# shemLamps.net
KiCad netlist of a schematic drawn in EAGLE
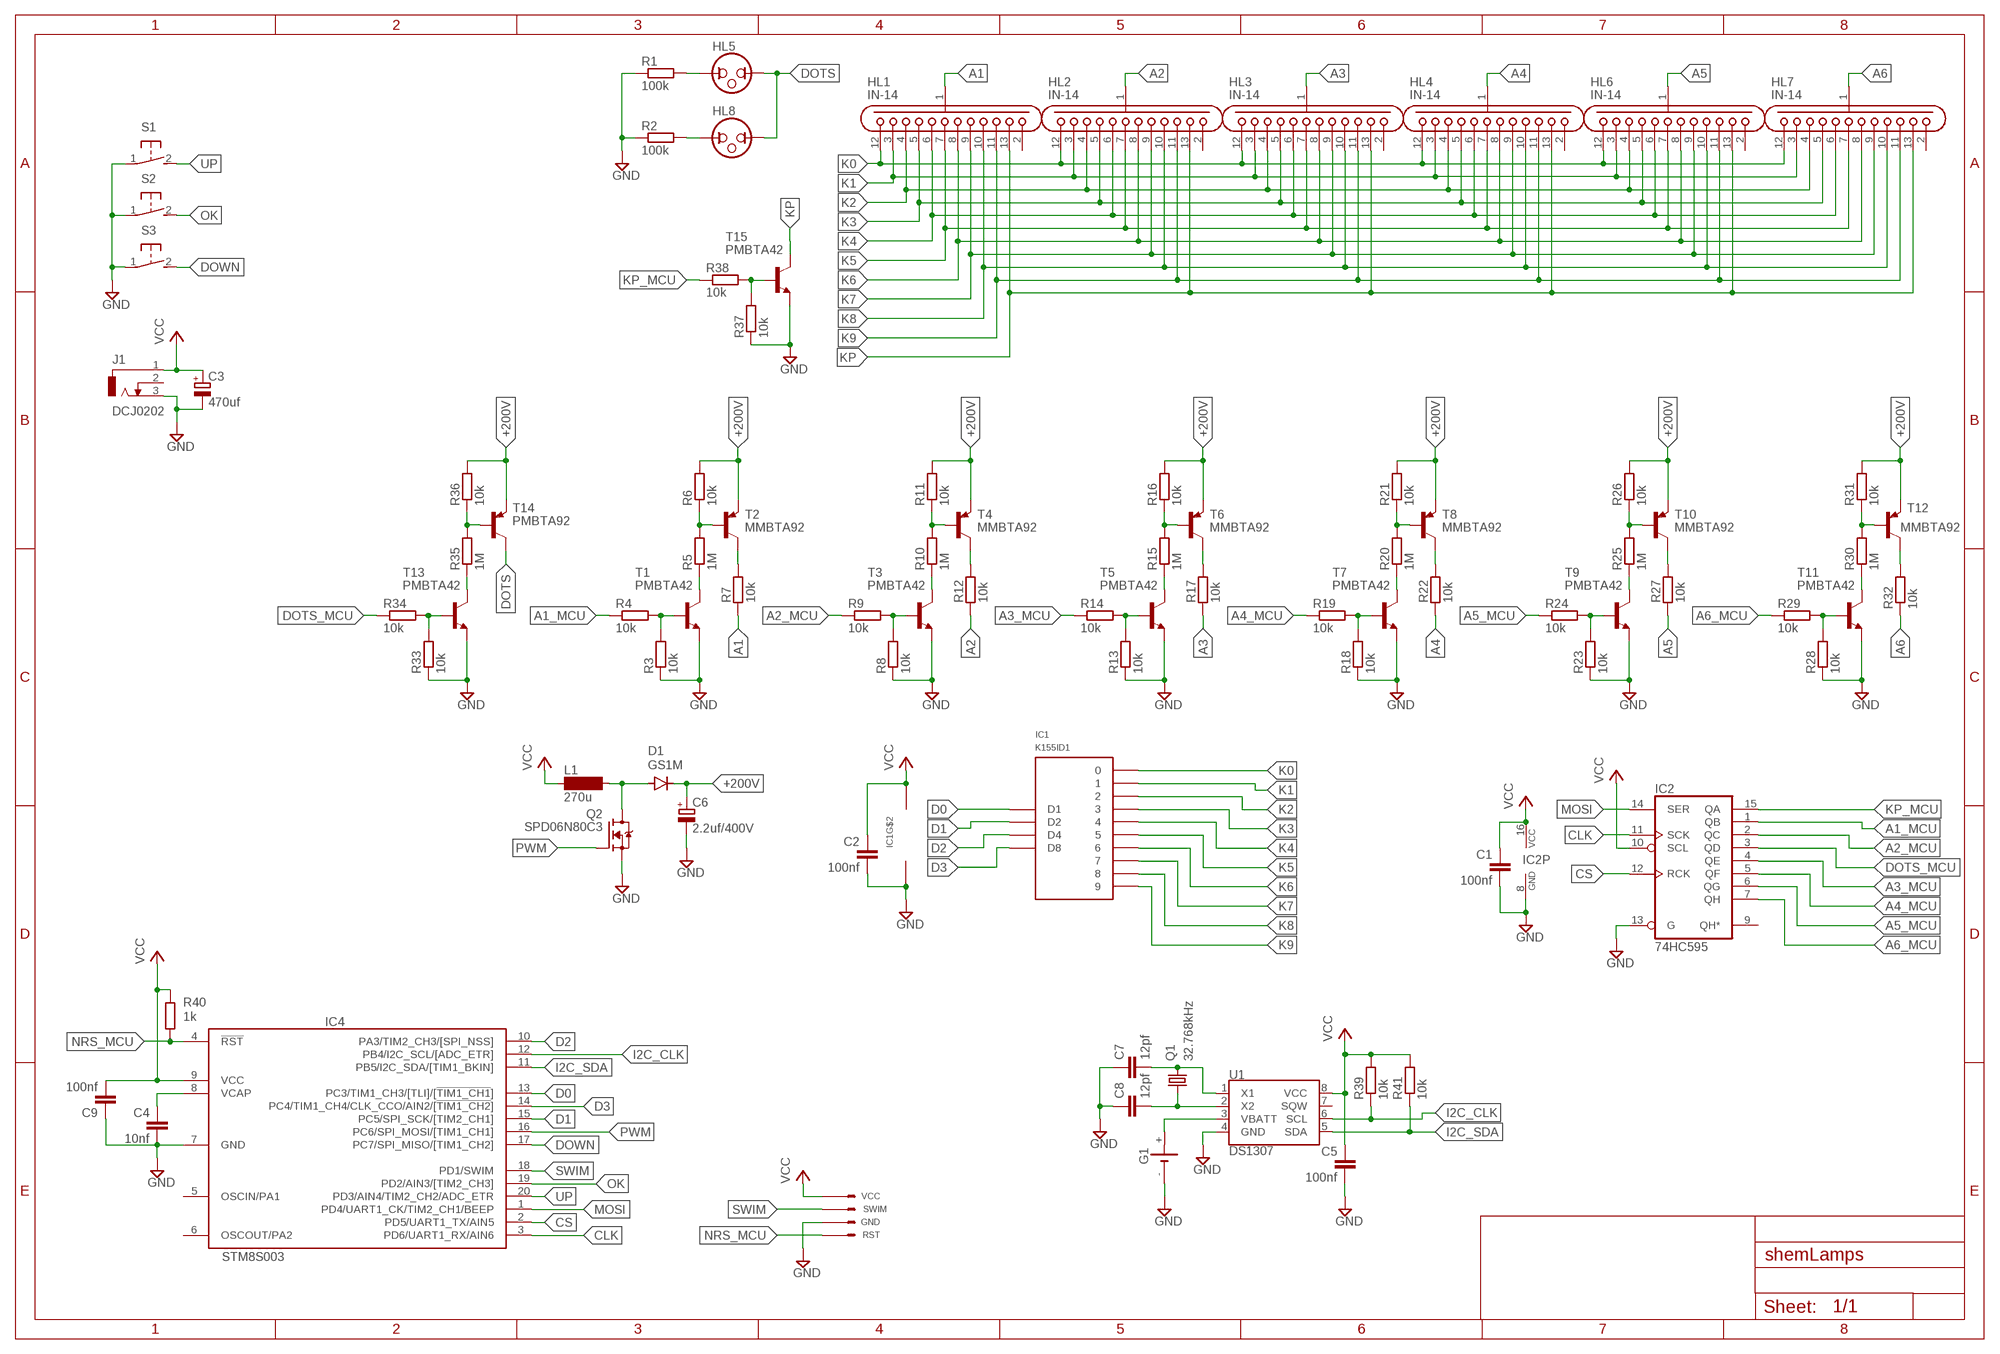
[diagram p0: schematic, sheet 1]

(export (version "E")
  (design (tool "Eeschema 10.0.6"))
  (components
    (comp (ref "C1")
      (value "100nf")
      (footprint "eagle-import:C0805")
      (libsource (lib "eagle-import") (part "CAP"))
    )
    (comp (ref "C2")
      (value "100nf")
      (footprint "eagle-import:C0805")
      (libsource (lib "eagle-import") (part "CAP"))
    )
    (comp (ref "C3")
      (value "470uf")
      (footprint "eagle-import:E3,5-8")
      (libsource (lib "eagle-import") (part "CPOL-EUE3.5-8"))
    )
    (comp (ref "C4")
      (value "10nf")
      (footprint "eagle-import:C0805")
      (libsource (lib "eagle-import") (part "CAP"))
    )
    (comp (ref "C5")
      (value "100nf")
      (footprint "eagle-import:C0805")
      (libsource (lib "eagle-import") (part "CAP"))
    )
    (comp (ref "C6")
      (value "2.2uf/400V")
      (footprint "eagle-import:E3,5-8")
      (libsource (lib "eagle-import") (part "CPOL-EUE3.5-8"))
    )
    (comp (ref "C7")
      (value "12pf")
      (footprint "eagle-import:C0805")
      (libsource (lib "eagle-import") (part "CAP"))
    )
    (comp (ref "C8")
      (value "12pf")
      (footprint "eagle-import:C0805")
      (libsource (lib "eagle-import") (part "CAP"))
    )
    (comp (ref "C9")
      (value "100nf")
      (footprint "eagle-import:C0805")
      (libsource (lib "eagle-import") (part "CAP"))
    )
    (comp (ref "D1")
      (value "GS1M")
      (footprint "eagle-import:DO-214AC")
      (libsource (lib "eagle-import") (part "DIODE-DO-214AC"))
    )
    (comp (ref "G1")
      (value "BATTERY")
      (footprint "eagle-import:CH291-1220LF_W")
      (libsource (lib "eagle-import") (part "BATTERY"))
    )
    (comp (ref "HL1")
      (value "IN-14")
      (footprint "eagle-import:IN-14")
      (libsource (lib "eagle-import") (part "IN-14"))
    )
    (comp (ref "HL2")
      (value "IN-14")
      (footprint "eagle-import:IN-14")
      (libsource (lib "eagle-import") (part "IN-14"))
    )
    (comp (ref "HL3")
      (value "IN-14")
      (footprint "eagle-import:IN-14")
      (libsource (lib "eagle-import") (part "IN-14"))
    )
    (comp (ref "HL4")
      (value "IN-14")
      (footprint "eagle-import:IN-14")
      (libsource (lib "eagle-import") (part "IN-14"))
    )
    (comp (ref "HL5")
      (value "NEON_LAMP")
      (footprint "eagle-import:NEON_LAMP")
      (libsource (lib "eagle-import") (part "NEON_LAMP"))
    )
    (comp (ref "HL6")
      (value "IN-14")
      (footprint "eagle-import:IN-14")
      (libsource (lib "eagle-import") (part "IN-14"))
    )
    (comp (ref "HL7")
      (value "IN-14")
      (footprint "eagle-import:IN-14")
      (libsource (lib "eagle-import") (part "IN-14"))
    )
    (comp (ref "HL8")
      (value "NEON_LAMP")
      (footprint "eagle-import:NEON_LAMP")
      (libsource (lib "eagle-import") (part "NEON_LAMP"))
    )
    (comp (ref "IC1")
      (value "K155ID1")
      (footprint "eagle-import:DIL16")
      (libsource (lib "eagle-import") (part "K155ID1"))
    )
    (comp (ref "IC2")
      (value "74HC595")
      (footprint "eagle-import:TSSOP16L")
      (libsource (lib "eagle-import") (part "74HC595"))
    )
    (comp (ref "IC4")
      (value "STM8S003")
      (footprint "eagle-import:TSSOP-20")
      (libsource (lib "eagle-import") (part "STM8S003"))
    )
    (comp (ref "J1")
      (value "DCJ0202")
      (footprint "eagle-import:DCJ0202")
      (libsource (lib "eagle-import") (part "DCJ0202"))
    )
    (comp (ref "L1")
      (value "270u")
      (footprint "eagle-import:BS11")
      (libsource (lib "eagle-import") (part "BS11"))
    )
    (comp (ref "Q1")
      (value "32.768kHz")
      (footprint "eagle-import:TC26H")
      (libsource (lib "eagle-import") (part "CRYSTALTC26H"))
    )
    (comp (ref "Q2")
      (value "SPD06N80C3")
      (footprint "eagle-import:TO252")
      (libsource (lib "eagle-import") (part "SPD06N80C3"))
    )
    (comp (ref "R1")
      (value "100k")
      (footprint "eagle-import:0207_10")
      (libsource (lib "eagle-import") (part "R-EU_0207/10"))
    )
    (comp (ref "R2")
      (value "100k")
      (footprint "eagle-import:0207_10")
      (libsource (lib "eagle-import") (part "R-EU_0207/10"))
    )
    (comp (ref "R3")
      (value "10k")
      (footprint "eagle-import:R0805")
      (libsource (lib "eagle-import") (part "RES"))
    )
    (comp (ref "R4")
      (value "10k")
      (footprint "eagle-import:R0805")
      (libsource (lib "eagle-import") (part "RES"))
    )
    (comp (ref "R5")
      (value "1M")
      (footprint "eagle-import:R0805")
      (libsource (lib "eagle-import") (part "RES"))
    )
    (comp (ref "R6")
      (value "10k")
      (footprint "eagle-import:R0805")
      (libsource (lib "eagle-import") (part "RES"))
    )
    (comp (ref "R7")
      (value "10k")
      (footprint "eagle-import:R0805")
      (libsource (lib "eagle-import") (part "RES"))
    )
    (comp (ref "R8")
      (value "10k")
      (footprint "eagle-import:R0805")
      (libsource (lib "eagle-import") (part "RES"))
    )
    (comp (ref "R9")
      (value "10k")
      (footprint "eagle-import:R0805")
      (libsource (lib "eagle-import") (part "RES"))
    )
    (comp (ref "R10")
      (value "1M")
      (footprint "eagle-import:R0805")
      (libsource (lib "eagle-import") (part "RES"))
    )
    (comp (ref "R11")
      (value "10k")
      (footprint "eagle-import:R0805")
      (libsource (lib "eagle-import") (part "RES"))
    )
    (comp (ref "R12")
      (value "10k")
      (footprint "eagle-import:R0805")
      (libsource (lib "eagle-import") (part "RES"))
    )
    (comp (ref "R13")
      (value "10k")
      (footprint "eagle-import:R0805")
      (libsource (lib "eagle-import") (part "RES"))
    )
    (comp (ref "R14")
      (value "10k")
      (footprint "eagle-import:R0805")
      (libsource (lib "eagle-import") (part "RES"))
    )
    (comp (ref "R15")
      (value "1M")
      (footprint "eagle-import:R0805")
      (libsource (lib "eagle-import") (part "RES"))
    )
    (comp (ref "R16")
      (value "10k")
      (footprint "eagle-import:R0805")
      (libsource (lib "eagle-import") (part "RES"))
    )
    (comp (ref "R17")
      (value "10k")
      (footprint "eagle-import:R0805")
      (libsource (lib "eagle-import") (part "RES"))
    )
    (comp (ref "R18")
      (value "10k")
      (footprint "eagle-import:R0805")
      (libsource (lib "eagle-import") (part "RES"))
    )
    (comp (ref "R19")
      (value "10k")
      (footprint "eagle-import:R0805")
      (libsource (lib "eagle-import") (part "RES"))
    )
    (comp (ref "R20")
      (value "1M")
      (footprint "eagle-import:R0805")
      (libsource (lib "eagle-import") (part "RES"))
    )
    (comp (ref "R21")
      (value "10k")
      (footprint "eagle-import:R0805")
      (libsource (lib "eagle-import") (part "RES"))
    )
    (comp (ref "R22")
      (value "10k")
      (footprint "eagle-import:R0805")
      (libsource (lib "eagle-import") (part "RES"))
    )
    (comp (ref "R23")
      (value "10k")
      (footprint "eagle-import:R0805")
      (libsource (lib "eagle-import") (part "RES"))
    )
    (comp (ref "R24")
      (value "10k")
      (footprint "eagle-import:R0805")
      (libsource (lib "eagle-import") (part "RES"))
    )
    (comp (ref "R25")
      (value "1M")
      (footprint "eagle-import:R0805")
      (libsource (lib "eagle-import") (part "RES"))
    )
    (comp (ref "R26")
      (value "10k")
      (footprint "eagle-import:R0805")
      (libsource (lib "eagle-import") (part "RES"))
    )
    (comp (ref "R27")
      (value "10k")
      (footprint "eagle-import:R0805")
      (libsource (lib "eagle-import") (part "RES"))
    )
    (comp (ref "R28")
      (value "10k")
      (footprint "eagle-import:R0805")
      (libsource (lib "eagle-import") (part "RES"))
    )
    (comp (ref "R29")
      (value "10k")
      (footprint "eagle-import:R0805")
      (libsource (lib "eagle-import") (part "RES"))
    )
    (comp (ref "R30")
      (value "1M")
      (footprint "eagle-import:R0805")
      (libsource (lib "eagle-import") (part "RES"))
    )
    (comp (ref "R31")
      (value "10k")
      (footprint "eagle-import:R0805")
      (libsource (lib "eagle-import") (part "RES"))
    )
    (comp (ref "R32")
      (value "10k")
      (footprint "eagle-import:R0805")
      (libsource (lib "eagle-import") (part "RES"))
    )
    (comp (ref "R33")
      (value "10k")
      (footprint "eagle-import:R0805")
      (libsource (lib "eagle-import") (part "RES"))
    )
    (comp (ref "R34")
      (value "10k")
      (footprint "eagle-import:R0805")
      (libsource (lib "eagle-import") (part "RES"))
    )
    (comp (ref "R35")
      (value "1M")
      (footprint "eagle-import:R0805")
      (libsource (lib "eagle-import") (part "RES"))
    )
    (comp (ref "R36")
      (value "10k")
      (footprint "eagle-import:R0805")
      (libsource (lib "eagle-import") (part "RES"))
    )
    (comp (ref "R37")
      (value "10k")
      (footprint "eagle-import:R0805")
      (libsource (lib "eagle-import") (part "RES"))
    )
    (comp (ref "R38")
      (value "10k")
      (footprint "eagle-import:R0805")
      (libsource (lib "eagle-import") (part "RES"))
    )
    (comp (ref "R39")
      (value "10k")
      (footprint "eagle-import:R0805")
      (libsource (lib "eagle-import") (part "RES"))
    )
    (comp (ref "R40")
      (value "1k")
      (footprint "eagle-import:R0805")
      (libsource (lib "eagle-import") (part "RES"))
    )
    (comp (ref "R41")
      (value "10k")
      (footprint "eagle-import:R0805")
      (libsource (lib "eagle-import") (part "RES"))
    )
    (comp (ref "S1")
      (value "31-XX")
      (footprint "eagle-import:B3F-31XX")
      (fields (field (name "MPN") "B3F-3100"))
      (libsource (lib "eagle-import") (part "31-XX"))
    )
    (comp (ref "S2")
      (value "31-XX")
      (footprint "eagle-import:B3F-31XX")
      (fields (field (name "MPN") "B3F-3100"))
      (libsource (lib "eagle-import") (part "31-XX"))
    )
    (comp (ref "S3")
      (value "31-XX")
      (footprint "eagle-import:B3F-31XX")
      (fields (field (name "MPN") "B3F-3100"))
      (libsource (lib "eagle-import") (part "31-XX"))
    )
    (comp (ref "SV1")
      (value "SWIM")
      (footprint "eagle-import:SWIM")
      (libsource (lib "eagle-import") (part "SWIM"))
    )
    (comp (ref "T1")
      (value "PMBTA42")
      (footprint "eagle-import:SOT23-BEC")
      (libsource (lib "eagle-import") (part "-NPN-SOT23-BECBC817-16"))
    )
    (comp (ref "T2")
      (value "MMBTA92")
      (footprint "eagle-import:SOT23-BEC")
      (libsource (lib "eagle-import") (part "-PNP-SOT23-BECBC807-16"))
    )
    (comp (ref "T3")
      (value "PMBTA42")
      (footprint "eagle-import:SOT23-BEC")
      (libsource (lib "eagle-import") (part "-NPN-SOT23-BECBC817-16"))
    )
    (comp (ref "T4")
      (value "MMBTA92")
      (footprint "eagle-import:SOT23-BEC")
      (libsource (lib "eagle-import") (part "-PNP-SOT23-BECBC807-16"))
    )
    (comp (ref "T5")
      (value "PMBTA42")
      (footprint "eagle-import:SOT23-BEC")
      (libsource (lib "eagle-import") (part "-NPN-SOT23-BECBC817-16"))
    )
    (comp (ref "T6")
      (value "MMBTA92")
      (footprint "eagle-import:SOT23-BEC")
      (libsource (lib "eagle-import") (part "-PNP-SOT23-BECBC807-16"))
    )
    (comp (ref "T7")
      (value "PMBTA42")
      (footprint "eagle-import:SOT23-BEC")
      (libsource (lib "eagle-import") (part "-NPN-SOT23-BECBC817-16"))
    )
    (comp (ref "T8")
      (value "MMBTA92")
      (footprint "eagle-import:SOT23-BEC")
      (libsource (lib "eagle-import") (part "-PNP-SOT23-BECBC807-16"))
    )
    (comp (ref "T9")
      (value "PMBTA42")
      (footprint "eagle-import:SOT23-BEC")
      (libsource (lib "eagle-import") (part "-NPN-SOT23-BECBC817-16"))
    )
    (comp (ref "T10")
      (value "MMBTA92")
      (footprint "eagle-import:SOT23-BEC")
      (libsource (lib "eagle-import") (part "-PNP-SOT23-BECBC807-16"))
    )
    (comp (ref "T11")
      (value "PMBTA42")
      (footprint "eagle-import:SOT23-BEC")
      (libsource (lib "eagle-import") (part "-NPN-SOT23-BECBC817-16"))
    )
    (comp (ref "T12")
      (value "MMBTA92")
      (footprint "eagle-import:SOT23-BEC")
      (libsource (lib "eagle-import") (part "-PNP-SOT23-BECBC807-16"))
    )
    (comp (ref "T13")
      (value "PMBTA42")
      (footprint "eagle-import:SOT23-BEC")
      (libsource (lib "eagle-import") (part "-NPN-SOT23-BECBC817-16"))
    )
    (comp (ref "T14")
      (value "PMBTA92")
      (footprint "eagle-import:SOT23-BEC")
      (libsource (lib "eagle-import") (part "-PNP-SOT23-BECBC807-16"))
    )
    (comp (ref "T15")
      (value "PMBTA42")
      (footprint "eagle-import:SOT23-BEC")
      (libsource (lib "eagle-import") (part "-NPN-SOT23-BECBC817-16"))
    )
    (comp (ref "U1")
      (value "DS1307")
      (footprint "eagle-import:SO08")
      (libsource (lib "eagle-import") (part "DS1307"))
    )
  )
  (nets
    (net (code "1") (name "+200V") (class "Default")
      (node (ref "C6") (pin "+") (pinfunction "+_+") (pintype "passive"))
      (node (ref "D1") (pin "C") (pinfunction "C_C") (pintype "passive"))
      (node (ref "R11") (pin "2") (pinfunction "2_2") (pintype "passive"))
      (node (ref "R16") (pin "2") (pinfunction "2_2") (pintype "passive"))
      (node (ref "R21") (pin "2") (pinfunction "2_2") (pintype "passive"))
      (node (ref "R26") (pin "2") (pinfunction "2_2") (pintype "passive"))
      (node (ref "R31") (pin "2") (pinfunction "2_2") (pintype "passive"))
      (node (ref "R36") (pin "2") (pinfunction "2_2") (pintype "passive"))
      (node (ref "R6") (pin "2") (pinfunction "2_2") (pintype "passive"))
      (node (ref "T10") (pin "E") (pinfunction "E_E") (pintype "passive"))
      (node (ref "T12") (pin "E") (pinfunction "E_E") (pintype "passive"))
      (node (ref "T14") (pin "E") (pinfunction "E_E") (pintype "passive"))
      (node (ref "T2") (pin "E") (pinfunction "E_E") (pintype "passive"))
      (node (ref "T4") (pin "E") (pinfunction "E_E") (pintype "passive"))
      (node (ref "T6") (pin "E") (pinfunction "E_E") (pintype "passive"))
      (node (ref "T8") (pin "E") (pinfunction "E_E") (pintype "passive"))
    )
    (net (code "2") (name "A1") (class "Default")
      (node (ref "HL1") (pin "1") (pinfunction "A_1") (pintype "passive"))
      (node (ref "R7") (pin "1") (pinfunction "1_1") (pintype "passive"))
    )
    (net (code "3") (name "A1_MCU") (class "Default")
      (node (ref "IC2") (pin "1") (pinfunction "QB_1") (pintype "tri_state"))
      (node (ref "R4") (pin "1") (pinfunction "1_1") (pintype "passive"))
    )
    (net (code "4") (name "A2") (class "Default")
      (node (ref "HL2") (pin "1") (pinfunction "A_1") (pintype "passive"))
      (node (ref "R12") (pin "1") (pinfunction "1_1") (pintype "passive"))
    )
    (net (code "5") (name "A2_MCU") (class "Default")
      (node (ref "IC2") (pin "2") (pinfunction "QC_2") (pintype "tri_state"))
      (node (ref "R9") (pin "1") (pinfunction "1_1") (pintype "passive"))
    )
    (net (code "6") (name "A3") (class "Default")
      (node (ref "HL3") (pin "1") (pinfunction "A_1") (pintype "passive"))
      (node (ref "R17") (pin "1") (pinfunction "1_1") (pintype "passive"))
    )
    (net (code "7") (name "A3_MCU") (class "Default")
      (node (ref "IC2") (pin "4") (pinfunction "QE_4") (pintype "tri_state"))
      (node (ref "R14") (pin "1") (pinfunction "1_1") (pintype "passive"))
    )
    (net (code "8") (name "A4") (class "Default")
      (node (ref "HL4") (pin "1") (pinfunction "A_1") (pintype "passive"))
      (node (ref "R22") (pin "1") (pinfunction "1_1") (pintype "passive"))
    )
    (net (code "9") (name "A4_MCU") (class "Default")
      (node (ref "IC2") (pin "5") (pinfunction "QF_5") (pintype "tri_state"))
      (node (ref "R19") (pin "1") (pinfunction "1_1") (pintype "passive"))
    )
    (net (code "10") (name "A5") (class "Default")
      (node (ref "HL6") (pin "1") (pinfunction "A_1") (pintype "passive"))
      (node (ref "R27") (pin "1") (pinfunction "1_1") (pintype "passive"))
    )
    (net (code "11") (name "A5_MCU") (class "Default")
      (node (ref "IC2") (pin "6") (pinfunction "QG_6") (pintype "tri_state"))
      (node (ref "R24") (pin "1") (pinfunction "1_1") (pintype "passive"))
    )
    (net (code "12") (name "A6") (class "Default")
      (node (ref "HL7") (pin "1") (pinfunction "A_1") (pintype "passive"))
      (node (ref "R32") (pin "1") (pinfunction "1_1") (pintype "passive"))
    )
    (net (code "13") (name "A6_MCU") (class "Default")
      (node (ref "IC2") (pin "7") (pinfunction "QH_7") (pintype "tri_state"))
      (node (ref "R29") (pin "1") (pinfunction "1_1") (pintype "passive"))
    )
    (net (code "14") (name "CLK") (class "Default")
      (node (ref "IC2") (pin "11") (pinfunction "SCK_11") (pintype "input"))
      (node (ref "IC4") (pin "3") (pinfunction "PD6/UART1_RX/AIN6_3") (pintype "bidirectional"))
    )
    (net (code "15") (name "CS") (class "Default")
      (node (ref "IC2") (pin "12") (pinfunction "RCK_12") (pintype "input"))
      (node (ref "IC4") (pin "2") (pinfunction "PD5/UART1_TX/AIN5_2") (pintype "bidirectional"))
    )
    (net (code "16") (name "D0") (class "Default")
      (node (ref "IC1") (pin "3") (pinfunction "D1_3") (pintype "input"))
      (node (ref "IC4") (pin "13") (pinfunction "PC3/TIM1_CH3/[TLI]/[~{TIM1_CH1}]_13") (pintype "bidirectional"))
    )
    (net (code "17") (name "D1") (class "Default")
      (node (ref "IC1") (pin "6") (pinfunction "D2_6") (pintype "input"))
      (node (ref "IC4") (pin "15") (pinfunction "PC5/SPI_SCK/[TIM2_CH1]_15") (pintype "bidirectional"))
    )
    (net (code "18") (name "D2") (class "Default")
      (node (ref "IC1") (pin "7") (pinfunction "D4_7") (pintype "input"))
      (node (ref "IC4") (pin "10") (pinfunction "PA3/TIM2_CH3/[SPI_NSS]_10") (pintype "bidirectional"))
    )
    (net (code "19") (name "D3") (class "Default")
      (node (ref "IC1") (pin "4") (pinfunction "D8_4") (pintype "input"))
      (node (ref "IC4") (pin "14") (pinfunction "PC4/TIM1_CH4/CLK_CCO/AIN2/[~{TIM1_CH2}]_14") (pintype "bidirectional"))
    )
    (net (code "20") (name "DOTS") (class "Default")
      (node (ref "HL5") (pin "2") (pinfunction "2_2") (pintype "passive"))
      (node (ref "HL8") (pin "2") (pinfunction "2_2") (pintype "passive"))
      (node (ref "T14") (pin "C") (pinfunction "C_C") (pintype "passive"))
    )
    (net (code "21") (name "DOTS_MCU") (class "Default")
      (node (ref "IC2") (pin "3") (pinfunction "QD_3") (pintype "tri_state"))
      (node (ref "R34") (pin "1") (pinfunction "1_1") (pintype "passive"))
    )
    (net (code "22") (name "DOWN") (class "Default")
      (node (ref "IC4") (pin "17") (pinfunction "PC7/SPI_MISO/[TIM1_CH2]_17") (pintype "bidirectional"))
      (node (ref "S3") (pin "2") (pinfunction "S_2") (pintype "passive"))
    )
    (net (code "23") (name "GND") (class "Default")
      (node (ref "C1") (pin "2") (pinfunction "2_2") (pintype "passive"))
      (node (ref "C2") (pin "2") (pinfunction "2_2") (pintype "passive"))
      (node (ref "C3") (pin "-") (pinfunction "-_-") (pintype "passive"))
      (node (ref "C4") (pin "2") (pinfunction "2_2") (pintype "passive"))
      (node (ref "C5") (pin "2") (pinfunction "2_2") (pintype "passive"))
      (node (ref "C6") (pin "-") (pinfunction "-_-") (pintype "passive"))
      (node (ref "C7") (pin "1") (pinfunction "1_1") (pintype "passive"))
      (node (ref "C8") (pin "1") (pinfunction "1_1") (pintype "passive"))
      (node (ref "C9") (pin "1") (pinfunction "1_1") (pintype "passive"))
      (node (ref "G1") (pin "-") (pinfunction "-_-") (pintype "passive"))
      (node (ref "IC1") (pin "12") (pinfunction "GND_12") (pintype "power_in"))
      (node (ref "IC2") (pin "13") (pinfunction "G_13") (pintype "input"))
      (node (ref "IC2") (pin "8") (pinfunction "GND_8") (pintype "power_in"))
      (node (ref "IC4") (pin "7") (pinfunction "GND_7") (pintype "power_in"))
      (node (ref "J1") (pin "3") (pinfunction "3_3") (pintype "passive"))
      (node (ref "Q2") (pin "2") (pinfunction "S_2") (pintype "passive"))
      (node (ref "R1") (pin "1") (pinfunction "1_1") (pintype "passive"))
      (node (ref "R13") (pin "1") (pinfunction "1_1") (pintype "passive"))
      (node (ref "R18") (pin "1") (pinfunction "1_1") (pintype "passive"))
      (node (ref "R2") (pin "1") (pinfunction "1_1") (pintype "passive"))
      (node (ref "R23") (pin "1") (pinfunction "1_1") (pintype "passive"))
      (node (ref "R28") (pin "1") (pinfunction "1_1") (pintype "passive"))
      (node (ref "R3") (pin "1") (pinfunction "1_1") (pintype "passive"))
      (node (ref "R33") (pin "1") (pinfunction "1_1") (pintype "passive"))
      (node (ref "R37") (pin "1") (pinfunction "1_1") (pintype "passive"))
      (node (ref "R8") (pin "1") (pinfunction "1_1") (pintype "passive"))
      (node (ref "S1") (pin "1") (pinfunction "P_1") (pintype "passive"))
      (node (ref "S2") (pin "1") (pinfunction "P_1") (pintype "passive"))
      (node (ref "S3") (pin "1") (pinfunction "P_1") (pintype "passive"))
      (node (ref "SV1") (pin "GND") (pinfunction "GND_GND") (pintype "power_in"))
      (node (ref "T1") (pin "E") (pinfunction "E_E") (pintype "passive"))
      (node (ref "T11") (pin "E") (pinfunction "E_E") (pintype "passive"))
      (node (ref "T13") (pin "E") (pinfunction "E_E") (pintype "passive"))
      (node (ref "T15") (pin "E") (pinfunction "E_E") (pintype "passive"))
      (node (ref "T3") (pin "E") (pinfunction "E_E") (pintype "passive"))
      (node (ref "T5") (pin "E") (pinfunction "E_E") (pintype "passive"))
      (node (ref "T7") (pin "E") (pinfunction "E_E") (pintype "passive"))
      (node (ref "T9") (pin "E") (pinfunction "E_E") (pintype "passive"))
      (node (ref "U1") (pin "4") (pinfunction "GND_4") (pintype "bidirectional"))
    )
    (net (code "24") (name "I2C_CLK") (class "Default")
      (node (ref "IC4") (pin "12") (pinfunction "PB4/I2C_SCL/[ADC_ETR]_12") (pintype "bidirectional"))
      (node (ref "R39") (pin "1") (pinfunction "1_1") (pintype "passive"))
      (node (ref "U1") (pin "6") (pinfunction "SCL_6") (pintype "bidirectional"))
    )
    (net (code "25") (name "I2C_SDA") (class "Default")
      (node (ref "IC4") (pin "11") (pinfunction "PB5/I2C_SDA/[TIM1_BKIN]_11") (pintype "bidirectional"))
      (node (ref "R41") (pin "1") (pinfunction "1_1") (pintype "passive"))
      (node (ref "U1") (pin "5") (pinfunction "SDA_5") (pintype "bidirectional"))
    )
    (net (code "26") (name "K0") (class "Default")
      (node (ref "HL1") (pin "12") (pinfunction "K0_12") (pintype "passive"))
      (node (ref "HL2") (pin "12") (pinfunction "K0_12") (pintype "passive"))
      (node (ref "HL3") (pin "12") (pinfunction "K0_12") (pintype "passive"))
      (node (ref "HL4") (pin "12") (pinfunction "K0_12") (pintype "passive"))
      (node (ref "HL6") (pin "12") (pinfunction "K0_12") (pintype "passive"))
      (node (ref "HL7") (pin "12") (pinfunction "K0_12") (pintype "passive"))
      (node (ref "IC1") (pin "16") (pinfunction "0_16") (pintype "output"))
    )
    (net (code "27") (name "K1") (class "Default")
      (node (ref "HL1") (pin "3") (pinfunction "K1_3") (pintype "passive"))
      (node (ref "HL2") (pin "3") (pinfunction "K1_3") (pintype "passive"))
      (node (ref "HL3") (pin "3") (pinfunction "K1_3") (pintype "passive"))
      (node (ref "HL4") (pin "3") (pinfunction "K1_3") (pintype "passive"))
      (node (ref "HL6") (pin "3") (pinfunction "K1_3") (pintype "passive"))
      (node (ref "HL7") (pin "3") (pinfunction "K1_3") (pintype "passive"))
      (node (ref "IC1") (pin "15") (pinfunction "1_15") (pintype "output"))
    )
    (net (code "28") (name "K2") (class "Default")
      (node (ref "HL1") (pin "4") (pinfunction "K2_4") (pintype "passive"))
      (node (ref "HL2") (pin "4") (pinfunction "K2_4") (pintype "passive"))
      (node (ref "HL3") (pin "4") (pinfunction "K2_4") (pintype "passive"))
      (node (ref "HL4") (pin "4") (pinfunction "K2_4") (pintype "passive"))
      (node (ref "HL6") (pin "4") (pinfunction "K2_4") (pintype "passive"))
      (node (ref "HL7") (pin "4") (pinfunction "K2_4") (pintype "passive"))
      (node (ref "IC1") (pin "8") (pinfunction "2_8") (pintype "output"))
    )
    (net (code "29") (name "K3") (class "Default")
      (node (ref "HL1") (pin "5") (pinfunction "K3_5") (pintype "passive"))
      (node (ref "HL2") (pin "5") (pinfunction "K3_5") (pintype "passive"))
      (node (ref "HL3") (pin "5") (pinfunction "K3_5") (pintype "passive"))
      (node (ref "HL4") (pin "5") (pinfunction "K3_5") (pintype "passive"))
      (node (ref "HL6") (pin "5") (pinfunction "K3_5") (pintype "passive"))
      (node (ref "HL7") (pin "5") (pinfunction "K3_5") (pintype "passive"))
      (node (ref "IC1") (pin "9") (pinfunction "3_9") (pintype "output"))
    )
    (net (code "30") (name "K4") (class "Default")
      (node (ref "HL1") (pin "6") (pinfunction "K4_6") (pintype "passive"))
      (node (ref "HL2") (pin "6") (pinfunction "K4_6") (pintype "passive"))
      (node (ref "HL3") (pin "6") (pinfunction "K4_6") (pintype "passive"))
      (node (ref "HL4") (pin "6") (pinfunction "K4_6") (pintype "passive"))
      (node (ref "HL6") (pin "6") (pinfunction "K4_6") (pintype "passive"))
      (node (ref "HL7") (pin "6") (pinfunction "K4_6") (pintype "passive"))
      (node (ref "IC1") (pin "13") (pinfunction "4_13") (pintype "output"))
    )
    (net (code "31") (name "K5") (class "Default")
      (node (ref "HL1") (pin "7") (pinfunction "K5_7") (pintype "passive"))
      (node (ref "HL2") (pin "7") (pinfunction "K5_7") (pintype "passive"))
      (node (ref "HL3") (pin "7") (pinfunction "K5_7") (pintype "passive"))
      (node (ref "HL4") (pin "7") (pinfunction "K5_7") (pintype "passive"))
      (node (ref "HL6") (pin "7") (pinfunction "K5_7") (pintype "passive"))
      (node (ref "HL7") (pin "7") (pinfunction "K5_7") (pintype "passive"))
      (node (ref "IC1") (pin "14") (pinfunction "5_14") (pintype "output"))
    )
    (net (code "32") (name "K6") (class "Default")
      (node (ref "HL1") (pin "8") (pinfunction "K6_8") (pintype "passive"))
      (node (ref "HL2") (pin "8") (pinfunction "K6_8") (pintype "passive"))
      (node (ref "HL3") (pin "8") (pinfunction "K6_8") (pintype "passive"))
      (node (ref "HL4") (pin "8") (pinfunction "K6_8") (pintype "passive"))
      (node (ref "HL6") (pin "8") (pinfunction "K6_8") (pintype "passive"))
      (node (ref "HL7") (pin "8") (pinfunction "K6_8") (pintype "passive"))
      (node (ref "IC1") (pin "11") (pinfunction "6_11") (pintype "output"))
    )
    (net (code "33") (name "K7") (class "Default")
      (node (ref "HL1") (pin "9") (pinfunction "K7_9") (pintype "passive"))
      (node (ref "HL2") (pin "9") (pinfunction "K7_9") (pintype "passive"))
      (node (ref "HL3") (pin "9") (pinfunction "K7_9") (pintype "passive"))
      (node (ref "HL4") (pin "9") (pinfunction "K7_9") (pintype "passive"))
      (node (ref "HL6") (pin "9") (pinfunction "K7_9") (pintype "passive"))
      (node (ref "HL7") (pin "9") (pinfunction "K7_9") (pintype "passive"))
      (node (ref "IC1") (pin "10") (pinfunction "7_10") (pintype "output"))
    )
    (net (code "34") (name "K8") (class "Default")
      (node (ref "HL1") (pin "10") (pinfunction "K8_10") (pintype "passive"))
      (node (ref "HL2") (pin "10") (pinfunction "K8_10") (pintype "passive"))
      (node (ref "HL3") (pin "10") (pinfunction "K8_10") (pintype "passive"))
      (node (ref "HL4") (pin "10") (pinfunction "K8_10") (pintype "passive"))
      (node (ref "HL6") (pin "10") (pinfunction "K8_10") (pintype "passive"))
      (node (ref "HL7") (pin "10") (pinfunction "K8_10") (pintype "passive"))
      (node (ref "IC1") (pin "1") (pinfunction "8_1") (pintype "output"))
    )
    (net (code "35") (name "K9") (class "Default")
      (node (ref "HL1") (pin "11") (pinfunction "K9_11") (pintype "passive"))
      (node (ref "HL2") (pin "11") (pinfunction "K9_11") (pintype "passive"))
      (node (ref "HL3") (pin "11") (pinfunction "K9_11") (pintype "passive"))
      (node (ref "HL4") (pin "11") (pinfunction "K9_11") (pintype "passive"))
      (node (ref "HL6") (pin "11") (pinfunction "K9_11") (pintype "passive"))
      (node (ref "HL7") (pin "11") (pinfunction "K9_11") (pintype "passive"))
      (node (ref "IC1") (pin "2") (pinfunction "9_2") (pintype "output"))
    )
    (net (code "36") (name "KP") (class "Default")
      (node (ref "HL1") (pin "13") (pinfunction "KK_13") (pintype "passive"))
      (node (ref "HL2") (pin "13") (pinfunction "KK_13") (pintype "passive"))
      (node (ref "HL3") (pin "13") (pinfunction "KK_13") (pintype "passive"))
      (node (ref "HL4") (pin "13") (pinfunction "KK_13") (pintype "passive"))
      (node (ref "HL6") (pin "13") (pinfunction "KK_13") (pintype "passive"))
      (node (ref "HL7") (pin "13") (pinfunction "KK_13") (pintype "passive"))
      (node (ref "T15") (pin "C") (pinfunction "C_C") (pintype "passive"))
    )
    (net (code "37") (name "KP_MCU") (class "Default")
      (node (ref "IC2") (pin "15") (pinfunction "QA_15") (pintype "tri_state"))
      (node (ref "R38") (pin "1") (pinfunction "1_1") (pintype "passive"))
    )
    (net (code "38") (name "MOSI") (class "Default")
      (node (ref "IC2") (pin "14") (pinfunction "SER_14") (pintype "input"))
      (node (ref "IC4") (pin "1") (pinfunction "PD4/UART1_CK/TIM2_CH1/BEEP_1") (pintype "bidirectional"))
    )
    (net (code "39") (name "NRS_MCU") (class "Default")
      (node (ref "IC4") (pin "4") (pinfunction "~{RST}_4") (pintype "input"))
      (node (ref "R40") (pin "1") (pinfunction "1_1") (pintype "passive"))
      (node (ref "SV1") (pin "NRS") (pinfunction "RST_NRS") (pintype "bidirectional"))
    )
    (net (code "40") (name "Net-(HL5-Pad1)") (class "Default")
      (node (ref "HL5") (pin "1") (pinfunction "1_1") (pintype "passive"))
      (node (ref "R1") (pin "2") (pinfunction "2_2") (pintype "passive"))
    )
    (net (code "41") (name "Net-(HL8-Pad1)") (class "Default")
      (node (ref "HL8") (pin "1") (pinfunction "1_1") (pintype "passive"))
      (node (ref "R2") (pin "2") (pinfunction "2_2") (pintype "passive"))
    )
    (net (code "42") (name "Net-(IC4-VCAP)") (class "Default")
      (node (ref "C4") (pin "1") (pinfunction "1_1") (pintype "passive"))
      (node (ref "IC4") (pin "8") (pinfunction "VCAP_8") (pintype "input"))
    )
    (net (code "43") (name "Net-(Q2-D)") (class "Default")
      (node (ref "D1") (pin "A") (pinfunction "A_A") (pintype "passive"))
      (node (ref "L1") (pin "2") (pinfunction "2_2") (pintype "passive"))
      (node (ref "Q2") (pin "3") (pinfunction "D_3") (pintype "passive"))
    )
    (net (code "44") (name "Net-(R3-Pad2)") (class "Default")
      (node (ref "R3") (pin "2") (pinfunction "2_2") (pintype "passive"))
      (node (ref "R4") (pin "2") (pinfunction "2_2") (pintype "passive"))
      (node (ref "T1") (pin "B") (pinfunction "B_B") (pintype "passive"))
    )
    (net (code "45") (name "Net-(R5-Pad1)") (class "Default")
      (node (ref "R5") (pin "1") (pinfunction "1_1") (pintype "passive"))
      (node (ref "T1") (pin "C") (pinfunction "C_C") (pintype "passive"))
    )
    (net (code "46") (name "Net-(R5-Pad2)") (class "Default")
      (node (ref "R5") (pin "2") (pinfunction "2_2") (pintype "passive"))
      (node (ref "R6") (pin "1") (pinfunction "1_1") (pintype "passive"))
      (node (ref "T2") (pin "B") (pinfunction "B_B") (pintype "passive"))
    )
    (net (code "47") (name "Net-(R7-Pad2)") (class "Default")
      (node (ref "R7") (pin "2") (pinfunction "2_2") (pintype "passive"))
      (node (ref "T2") (pin "C") (pinfunction "C_C") (pintype "passive"))
    )
    (net (code "48") (name "Net-(R8-Pad2)") (class "Default")
      (node (ref "R8") (pin "2") (pinfunction "2_2") (pintype "passive"))
      (node (ref "R9") (pin "2") (pinfunction "2_2") (pintype "passive"))
      (node (ref "T3") (pin "B") (pinfunction "B_B") (pintype "passive"))
    )
    (net (code "49") (name "Net-(R10-Pad1)") (class "Default")
      (node (ref "R10") (pin "1") (pinfunction "1_1") (pintype "passive"))
      (node (ref "T3") (pin "C") (pinfunction "C_C") (pintype "passive"))
    )
    (net (code "50") (name "Net-(R10-Pad2)") (class "Default")
      (node (ref "R10") (pin "2") (pinfunction "2_2") (pintype "passive"))
      (node (ref "R11") (pin "1") (pinfunction "1_1") (pintype "passive"))
      (node (ref "T4") (pin "B") (pinfunction "B_B") (pintype "passive"))
    )
    (net (code "51") (name "Net-(R12-Pad2)") (class "Default")
      (node (ref "R12") (pin "2") (pinfunction "2_2") (pintype "passive"))
      (node (ref "T4") (pin "C") (pinfunction "C_C") (pintype "passive"))
    )
    (net (code "52") (name "Net-(R13-Pad2)") (class "Default")
      (node (ref "R13") (pin "2") (pinfunction "2_2") (pintype "passive"))
      (node (ref "R14") (pin "2") (pinfunction "2_2") (pintype "passive"))
      (node (ref "T5") (pin "B") (pinfunction "B_B") (pintype "passive"))
    )
    (net (code "53") (name "Net-(R15-Pad1)") (class "Default")
      (node (ref "R15") (pin "1") (pinfunction "1_1") (pintype "passive"))
      (node (ref "T5") (pin "C") (pinfunction "C_C") (pintype "passive"))
    )
    (net (code "54") (name "Net-(R15-Pad2)") (class "Default")
      (node (ref "R15") (pin "2") (pinfunction "2_2") (pintype "passive"))
      (node (ref "R16") (pin "1") (pinfunction "1_1") (pintype "passive"))
      (node (ref "T6") (pin "B") (pinfunction "B_B") (pintype "passive"))
    )
    (net (code "55") (name "Net-(R17-Pad2)") (class "Default")
      (node (ref "R17") (pin "2") (pinfunction "2_2") (pintype "passive"))
      (node (ref "T6") (pin "C") (pinfunction "C_C") (pintype "passive"))
    )
    (net (code "56") (name "Net-(R18-Pad2)") (class "Default")
      (node (ref "R18") (pin "2") (pinfunction "2_2") (pintype "passive"))
      (node (ref "R19") (pin "2") (pinfunction "2_2") (pintype "passive"))
      (node (ref "T7") (pin "B") (pinfunction "B_B") (pintype "passive"))
    )
    (net (code "57") (name "Net-(R20-Pad1)") (class "Default")
      (node (ref "R20") (pin "1") (pinfunction "1_1") (pintype "passive"))
      (node (ref "T7") (pin "C") (pinfunction "C_C") (pintype "passive"))
    )
    (net (code "58") (name "Net-(R20-Pad2)") (class "Default")
      (node (ref "R20") (pin "2") (pinfunction "2_2") (pintype "passive"))
      (node (ref "R21") (pin "1") (pinfunction "1_1") (pintype "passive"))
      (node (ref "T8") (pin "B") (pinfunction "B_B") (pintype "passive"))
    )
    (net (code "59") (name "Net-(R22-Pad2)") (class "Default")
      (node (ref "R22") (pin "2") (pinfunction "2_2") (pintype "passive"))
      (node (ref "T8") (pin "C") (pinfunction "C_C") (pintype "passive"))
    )
    (net (code "60") (name "Net-(R23-Pad2)") (class "Default")
      (node (ref "R23") (pin "2") (pinfunction "2_2") (pintype "passive"))
      (node (ref "R24") (pin "2") (pinfunction "2_2") (pintype "passive"))
      (node (ref "T9") (pin "B") (pinfunction "B_B") (pintype "passive"))
    )
    (net (code "61") (name "Net-(R25-Pad1)") (class "Default")
      (node (ref "R25") (pin "1") (pinfunction "1_1") (pintype "passive"))
      (node (ref "T9") (pin "C") (pinfunction "C_C") (pintype "passive"))
    )
    (net (code "62") (name "Net-(R25-Pad2)") (class "Default")
      (node (ref "R25") (pin "2") (pinfunction "2_2") (pintype "passive"))
      (node (ref "R26") (pin "1") (pinfunction "1_1") (pintype "passive"))
      (node (ref "T10") (pin "B") (pinfunction "B_B") (pintype "passive"))
    )
    (net (code "63") (name "Net-(R27-Pad2)") (class "Default")
      (node (ref "R27") (pin "2") (pinfunction "2_2") (pintype "passive"))
      (node (ref "T10") (pin "C") (pinfunction "C_C") (pintype "passive"))
    )
    (net (code "64") (name "Net-(R28-Pad2)") (class "Default")
      (node (ref "R28") (pin "2") (pinfunction "2_2") (pintype "passive"))
      (node (ref "R29") (pin "2") (pinfunction "2_2") (pintype "passive"))
      (node (ref "T11") (pin "B") (pinfunction "B_B") (pintype "passive"))
    )
    (net (code "65") (name "Net-(R30-Pad1)") (class "Default")
      (node (ref "R30") (pin "1") (pinfunction "1_1") (pintype "passive"))
      (node (ref "T11") (pin "C") (pinfunction "C_C") (pintype "passive"))
    )
    (net (code "66") (name "Net-(R30-Pad2)") (class "Default")
      (node (ref "R30") (pin "2") (pinfunction "2_2") (pintype "passive"))
      (node (ref "R31") (pin "1") (pinfunction "1_1") (pintype "passive"))
      (node (ref "T12") (pin "B") (pinfunction "B_B") (pintype "passive"))
    )
    (net (code "67") (name "Net-(R32-Pad2)") (class "Default")
      (node (ref "R32") (pin "2") (pinfunction "2_2") (pintype "passive"))
      (node (ref "T12") (pin "C") (pinfunction "C_C") (pintype "passive"))
    )
    (net (code "68") (name "Net-(R33-Pad2)") (class "Default")
      (node (ref "R33") (pin "2") (pinfunction "2_2") (pintype "passive"))
      (node (ref "R34") (pin "2") (pinfunction "2_2") (pintype "passive"))
      (node (ref "T13") (pin "B") (pinfunction "B_B") (pintype "passive"))
    )
    (net (code "69") (name "Net-(R35-Pad1)") (class "Default")
      (node (ref "R35") (pin "1") (pinfunction "1_1") (pintype "passive"))
      (node (ref "T13") (pin "C") (pinfunction "C_C") (pintype "passive"))
    )
    (net (code "70") (name "Net-(R35-Pad2)") (class "Default")
      (node (ref "R35") (pin "2") (pinfunction "2_2") (pintype "passive"))
      (node (ref "R36") (pin "1") (pinfunction "1_1") (pintype "passive"))
      (node (ref "T14") (pin "B") (pinfunction "B_B") (pintype "passive"))
    )
    (net (code "71") (name "Net-(R37-Pad2)") (class "Default")
      (node (ref "R37") (pin "2") (pinfunction "2_2") (pintype "passive"))
      (node (ref "R38") (pin "2") (pinfunction "2_2") (pintype "passive"))
      (node (ref "T15") (pin "B") (pinfunction "B_B") (pintype "passive"))
    )
    (net (code "72") (name "Net-(U1-VBATT)") (class "Default")
      (node (ref "G1") (pin "+") (pinfunction "+_+") (pintype "passive"))
      (node (ref "U1") (pin "3") (pinfunction "VBATT_3") (pintype "bidirectional"))
    )
    (net (code "73") (name "Net-(U1-X1)") (class "Default")
      (node (ref "C7") (pin "2") (pinfunction "2_2") (pintype "passive"))
      (node (ref "Q1") (pin "1") (pinfunction "1_1") (pintype "passive"))
      (node (ref "U1") (pin "1") (pinfunction "X1_1") (pintype "bidirectional"))
    )
    (net (code "74") (name "Net-(U1-X2)") (class "Default")
      (node (ref "C8") (pin "2") (pinfunction "2_2") (pintype "passive"))
      (node (ref "Q1") (pin "2") (pinfunction "2_2") (pintype "passive"))
      (node (ref "U1") (pin "2") (pinfunction "X2_2") (pintype "bidirectional"))
    )
    (net (code "75") (name "OK") (class "Default")
      (node (ref "IC4") (pin "19") (pinfunction "PD2/AIN3/[TIM2_CH3]_19") (pintype "bidirectional"))
      (node (ref "S2") (pin "2") (pinfunction "S_2") (pintype "passive"))
    )
    (net (code "76") (name "PWM") (class "Default")
      (node (ref "IC4") (pin "16") (pinfunction "PC6/SPI_MOSI/[TIM1_CH1]_16") (pintype "bidirectional"))
      (node (ref "Q2") (pin "1") (pinfunction "G_1") (pintype "passive"))
    )
    (net (code "77") (name "SWIM") (class "Default")
      (node (ref "IC4") (pin "18") (pinfunction "PD1/SWIM_18") (pintype "bidirectional"))
      (node (ref "SV1") (pin "SWIM") (pinfunction "SWIM_SWIM") (pintype "bidirectional"))
    )
    (net (code "78") (name "UP") (class "Default")
      (node (ref "IC4") (pin "20") (pinfunction "PD3/AIN4/TIM2_CH2/ADC_ETR_20") (pintype "bidirectional"))
      (node (ref "S1") (pin "2") (pinfunction "S_2") (pintype "passive"))
    )
    (net (code "79") (name "VCC") (class "Default")
      (node (ref "C1") (pin "1") (pinfunction "1_1") (pintype "passive"))
      (node (ref "C2") (pin "1") (pinfunction "1_1") (pintype "passive"))
      (node (ref "C3") (pin "+") (pinfunction "+_+") (pintype "passive"))
      (node (ref "C5") (pin "1") (pinfunction "1_1") (pintype "passive"))
      (node (ref "C9") (pin "2") (pinfunction "2_2") (pintype "passive"))
      (node (ref "IC1") (pin "5") (pinfunction "VCC_5") (pintype "power_in"))
      (node (ref "IC2") (pin "10") (pinfunction "SCL_10") (pintype "input"))
      (node (ref "IC2") (pin "16") (pinfunction "VCC_16") (pintype "power_in"))
      (node (ref "IC4") (pin "9") (pinfunction "VCC_9") (pintype "power_in"))
      (node (ref "J1") (pin "1") (pinfunction "1_1") (pintype "passive"))
      (node (ref "L1") (pin "1") (pinfunction "1_1") (pintype "passive"))
      (node (ref "R39") (pin "2") (pinfunction "2_2") (pintype "passive"))
      (node (ref "R40") (pin "2") (pinfunction "2_2") (pintype "passive"))
      (node (ref "R41") (pin "2") (pinfunction "2_2") (pintype "passive"))
      (node (ref "SV1") (pin "VCC") (pinfunction "VCC_VCC") (pintype "power_in"))
      (node (ref "U1") (pin "8") (pinfunction "VCC_8") (pintype "bidirectional"))
    )
    (net (code "80") (name "unconnected-(HL1-KK2-Pad2)") (class "Default")
      (node (ref "HL1") (pin "2") (pinfunction "KK2_2") (pintype "passive"))
    )
    (net (code "81") (name "unconnected-(HL2-KK2-Pad2)") (class "Default")
      (node (ref "HL2") (pin "2") (pinfunction "KK2_2") (pintype "passive"))
    )
    (net (code "82") (name "unconnected-(HL3-KK2-Pad2)") (class "Default")
      (node (ref "HL3") (pin "2") (pinfunction "KK2_2") (pintype "passive"))
    )
    (net (code "83") (name "unconnected-(HL4-KK2-Pad2)") (class "Default")
      (node (ref "HL4") (pin "2") (pinfunction "KK2_2") (pintype "passive"))
    )
    (net (code "84") (name "unconnected-(HL6-KK2-Pad2)") (class "Default")
      (node (ref "HL6") (pin "2") (pinfunction "KK2_2") (pintype "passive"))
    )
    (net (code "85") (name "unconnected-(HL7-KK2-Pad2)") (class "Default")
      (node (ref "HL7") (pin "2") (pinfunction "KK2_2") (pintype "passive"))
    )
    (net (code "86") (name "unconnected-(IC2A-QH*-Pad9)") (class "Default")
      (node (ref "IC2") (pin "9") (pinfunction "QH*_9") (pintype "tri_state"))
    )
    (net (code "87") (name "unconnected-(IC4-OSCIN{slash}PA1-Pad5)") (class "Default")
      (node (ref "IC4") (pin "5") (pinfunction "OSCIN/PA1_5") (pintype "bidirectional"))
    )
    (net (code "88") (name "unconnected-(IC4-OSCOUT{slash}PA2-Pad6)") (class "Default")
      (node (ref "IC4") (pin "6") (pinfunction "OSCOUT/PA2_6") (pintype "bidirectional"))
    )
    (net (code "89") (name "unconnected-(J1-Pad2)") (class "Default")
      (node (ref "J1") (pin "2") (pinfunction "2_2") (pintype "passive"))
    )
    (net (code "90") (name "unconnected-(U1-SQW-Pad7)") (class "Default")
      (node (ref "U1") (pin "7") (pinfunction "SQW_7") (pintype "bidirectional"))
    )
  )
)
